# Led_And_Sound.net
KiCad netlist of a schematic drawn in Altium Designer
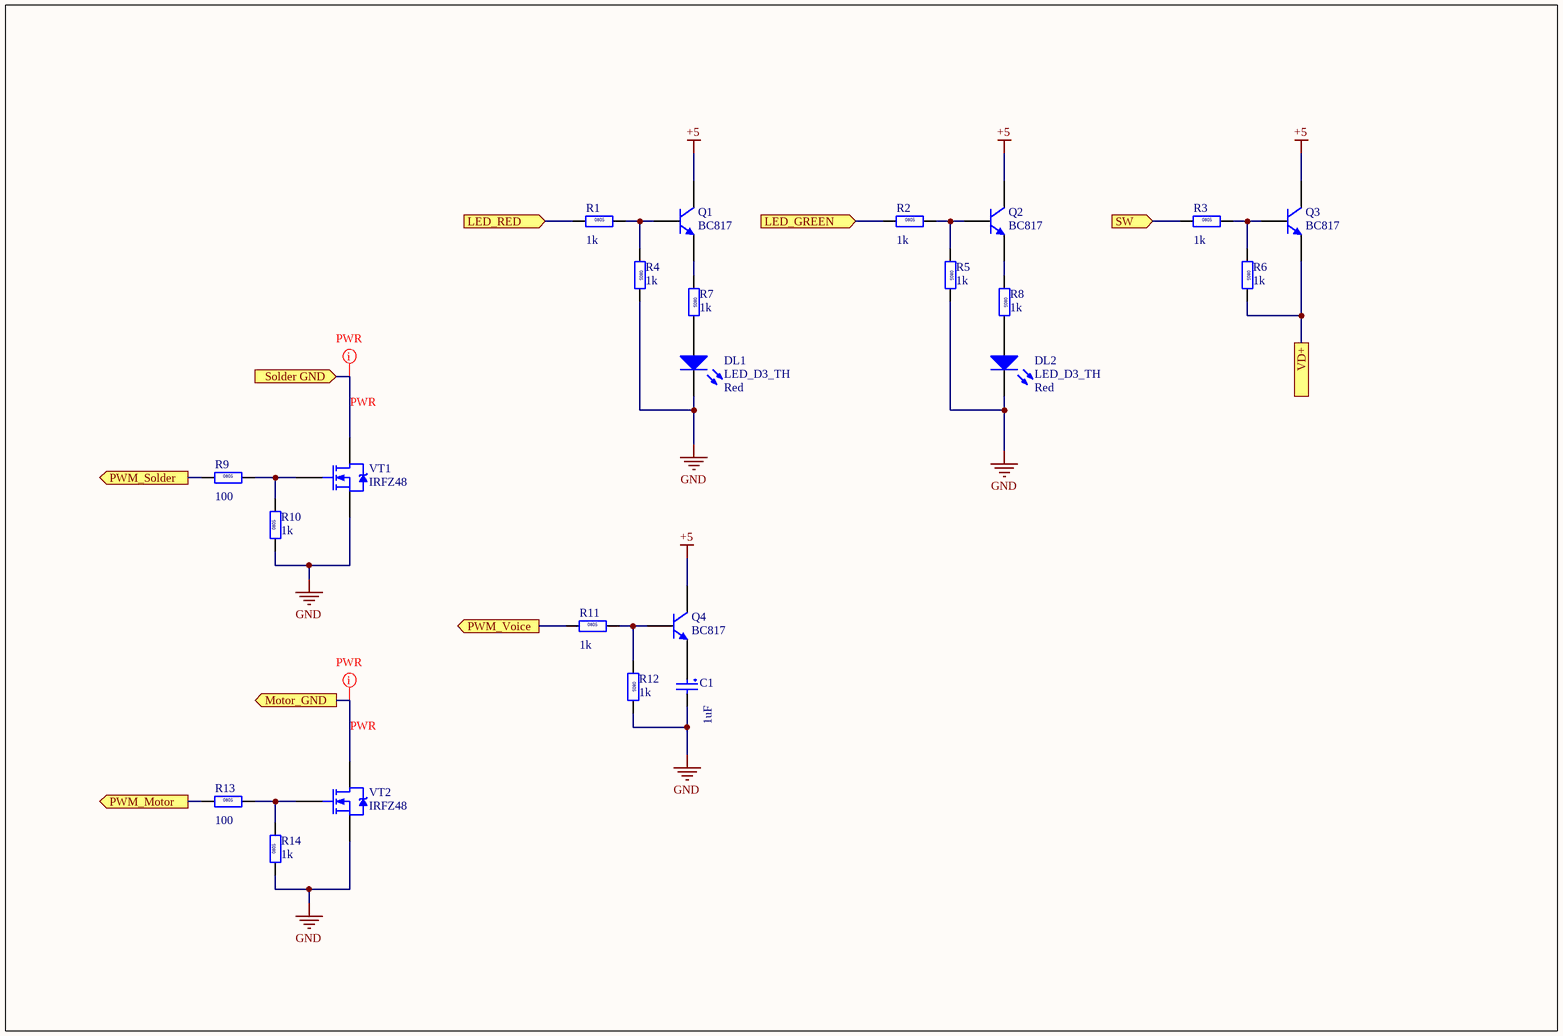
[diagram p0: Led_And_Sound.SchDoc]

(export (version "E")
  (design (tool "Eeschema 10.0.6"))
  (components
    (comp (ref "C1")
      (value "1uF")
      (footprint "ECAP1325")
      (description "Capacitor electrolytic 5 mm pitch, 13*25 body")
      (fields (field (name "Comment") "ECAP-1325"))
      (libsource (lib "Passive") (part "ECAP-1325"))
    )
    (comp (ref "DL1")
      (value "LED_D3_TH")
      (footprint "LED_D3_TH")
      (description "LED Through hole D3mm")
      (fields (field (name "ALTIUM_VALUE") "Red"))
      (libsource (lib "Discrete") (part "LED_D3_TH"))
    )
    (comp (ref "DL2")
      (value "LED_D3_TH")
      (footprint "LED_D3_TH")
      (description "LED Through hole D3mm")
      (fields (field (name "ALTIUM_VALUE") "Red"))
      (libsource (lib "Discrete") (part "LED_D3_TH"))
    )
    (comp (ref "Q1")
      (value "BC817")
      (footprint "SOT23-3M")
      (description "BC817 NPN Transistor")
      (libsource (lib "Discrete") (part "BC817"))
    )
    (comp (ref "Q2")
      (value "BC817")
      (footprint "SOT23-3M")
      (description "BC817 NPN Transistor")
      (libsource (lib "Discrete") (part "BC817"))
    )
    (comp (ref "Q3")
      (value "BC817")
      (footprint "SOT23-3M")
      (description "BC817 NPN Transistor")
      (libsource (lib "Discrete") (part "BC817"))
    )
    (comp (ref "Q4")
      (value "BC817")
      (footprint "SOT23-3M")
      (description "BC817 NPN Transistor")
      (libsource (lib "Discrete") (part "BC817"))
    )
    (comp (ref "R1")
      (value "1k")
      (footprint "RESC2012-0805M")
      (description "Resistor 0805")
      (fields (field (name "Comment") "RESC_0805_R"))
      (libsource (lib "") (part "RESC_0805_R_2"))
    )
    (comp (ref "R2")
      (value "1k")
      (footprint "RESC2012-0805M")
      (description "Resistor 0805")
      (fields (field (name "Comment") "RESC_0805_R"))
      (libsource (lib "") (part "RESC_0805_R_2"))
    )
    (comp (ref "R3")
      (value "1k")
      (footprint "RESC2012-0805M")
      (description "Resistor 0805")
      (fields (field (name "Comment") "RESC_0805_R"))
      (libsource (lib "") (part "RESC_0805_R_2"))
    )
    (comp (ref "R4")
      (value "1k")
      (footprint "RESC2012-0805M")
      (description "Resistor 0805")
      (fields (field (name "Comment") "RESC_0805_R"))
      (libsource (lib "") (part "RESC_0805_R_1"))
    )
    (comp (ref "R5")
      (value "1k")
      (footprint "RESC2012-0805M")
      (description "Resistor 0805")
      (fields (field (name "Comment") "RESC_0805_R"))
      (libsource (lib "") (part "RESC_0805_R_1"))
    )
    (comp (ref "R6")
      (value "1k")
      (footprint "RESC2012-0805M")
      (description "Resistor 0805")
      (fields (field (name "Comment") "RESC_0805_R"))
      (libsource (lib "") (part "RESC_0805_R_1"))
    )
    (comp (ref "R7")
      (value "1k")
      (footprint "RESC2012-0805M")
      (description "Resistor 0805")
      (fields (field (name "Comment") "RESC_0805_R"))
      (libsource (lib "") (part "RESC_0805_R_1"))
    )
    (comp (ref "R8")
      (value "1k")
      (footprint "RESC2012-0805M")
      (description "Resistor 0805")
      (fields (field (name "Comment") "RESC_0805_R"))
      (libsource (lib "") (part "RESC_0805_R_1"))
    )
    (comp (ref "R9")
      (value "100")
      (footprint "RESC2012-0805M")
      (description "Resistor 0805")
      (fields (field (name "Comment") "RESC_0805_R"))
      (libsource (lib "") (part "RESC_0805_R_2"))
    )
    (comp (ref "R10")
      (value "1k")
      (footprint "RESC2012-0805M")
      (description "Resistor 0805")
      (fields (field (name "Comment") "RESC_0805_R"))
      (libsource (lib "Passive") (part "RESC_0805_R"))
    )
    (comp (ref "R11")
      (value "1k")
      (footprint "RESC2012-0805M")
      (description "Resistor 0805")
      (fields (field (name "Comment") "RESC_0805_R"))
      (libsource (lib "") (part "RESC_0805_R_2"))
    )
    (comp (ref "R12")
      (value "1k")
      (footprint "RESC2012-0805M")
      (description "Resistor 0805")
      (fields (field (name "Comment") "RESC_0805_R"))
      (libsource (lib "") (part "RESC_0805_R_1"))
    )
    (comp (ref "R13")
      (value "100")
      (footprint "RESC2012-0805M")
      (description "Resistor 0805")
      (fields (field (name "Comment") "RESC_0805_R"))
      (libsource (lib "") (part "RESC_0805_R_2"))
    )
    (comp (ref "R14")
      (value "1k")
      (footprint "RESC2012-0805M")
      (description "Resistor 0805")
      (fields (field (name "Comment") "RESC_0805_R"))
      (libsource (lib "Passive") (part "RESC_0805_R"))
    )
    (comp (ref "VT1")
      (value "IRFZ48")
      (footprint "TO-220")
      (description "HEXFET N-Channel Power MOSFET")
      (fields (field (name "PUBLISHER") "Altium Limited"))
      (libsource (lib "Discrete") (part "IRFZ48"))
    )
    (comp (ref "VT2")
      (value "IRFZ48")
      (footprint "TO-220")
      (description "HEXFET N-Channel Power MOSFET")
      (fields (field (name "PUBLISHER") "Altium Limited"))
      (libsource (lib "Discrete") (part "IRFZ48"))
    )
  )
  (nets
    (net (code "1") (name "+5") (class "Default")
      (node (ref "Q1") (pin "3") (pinfunction "C_3") (pintype "passive"))
      (node (ref "Q2") (pin "3") (pinfunction "C_3") (pintype "passive"))
      (node (ref "Q3") (pin "3") (pinfunction "C_3") (pintype "passive"))
      (node (ref "Q4") (pin "3") (pinfunction "C_3") (pintype "passive"))
    )
    (net (code "2") (name "/LED_GREEN") (class "Default")
      (node (ref "R2") (pin "1") (pinfunction "1_1") (pintype "passive"))
    )
    (net (code "3") (name "/LED_RED") (class "Default")
      (node (ref "R1") (pin "1") (pinfunction "1_1") (pintype "passive"))
    )
    (net (code "4") (name "/Motor_GND") (class "Default")
      (node (ref "VT2") (pin "2") (pinfunction "D_2") (pintype "passive"))
    )
    (net (code "5") (name "/PWM_Motor") (class "Default")
      (node (ref "R13") (pin "1") (pinfunction "1_1") (pintype "passive"))
    )
    (net (code "6") (name "/PWM_Solder") (class "Default")
      (node (ref "R9") (pin "1") (pinfunction "1_1") (pintype "passive"))
    )
    (net (code "7") (name "/PWM_Voice") (class "Default")
      (node (ref "R11") (pin "1") (pinfunction "1_1") (pintype "passive"))
    )
    (net (code "8") (name "/SW") (class "Default")
      (node (ref "R3") (pin "1") (pinfunction "1_1") (pintype "passive"))
    )
    (net (code "9") (name "/Solder GND") (class "Default")
      (node (ref "VT1") (pin "2") (pinfunction "D_2") (pintype "passive"))
    )
    (net (code "10") (name "/VD+") (class "Default")
      (node (ref "Q3") (pin "2") (pinfunction "E_2") (pintype "passive"))
      (node (ref "R6") (pin "2") (pinfunction "2_2") (pintype "passive"))
    )
    (net (code "11") (name "GND") (class "Default")
      (node (ref "C1") (pin "2") (pinfunction "2_2") (pintype "passive"))
      (node (ref "DL1") (pin "2") (pinfunction "K_2") (pintype "passive"))
      (node (ref "DL2") (pin "2") (pinfunction "K_2") (pintype "passive"))
      (node (ref "R10") (pin "1") (pinfunction "1_1") (pintype "passive"))
      (node (ref "R12") (pin "2") (pinfunction "2_2") (pintype "passive"))
      (node (ref "R14") (pin "1") (pinfunction "1_1") (pintype "passive"))
      (node (ref "R4") (pin "2") (pinfunction "2_2") (pintype "passive"))
      (node (ref "R5") (pin "2") (pinfunction "2_2") (pintype "passive"))
      (node (ref "VT1") (pin "3") (pinfunction "S_3") (pintype "passive"))
      (node (ref "VT2") (pin "3") (pinfunction "S_3") (pintype "passive"))
    )
    (net (code "12") (name "Net-(DL1-A)") (class "Default")
      (node (ref "DL1") (pin "1") (pinfunction "A_1") (pintype "passive"))
      (node (ref "R7") (pin "2") (pinfunction "2_2") (pintype "passive"))
    )
    (net (code "13") (name "Net-(DL2-A)") (class "Default")
      (node (ref "DL2") (pin "1") (pinfunction "A_1") (pintype "passive"))
      (node (ref "R8") (pin "2") (pinfunction "2_2") (pintype "passive"))
    )
    (net (code "14") (name "Net-(Q1-B)") (class "Default")
      (node (ref "Q1") (pin "1") (pinfunction "B_1") (pintype "passive"))
      (node (ref "R1") (pin "2") (pinfunction "2_2") (pintype "passive"))
      (node (ref "R4") (pin "1") (pinfunction "1_1") (pintype "passive"))
    )
    (net (code "15") (name "Net-(Q1-E)") (class "Default")
      (node (ref "Q1") (pin "2") (pinfunction "E_2") (pintype "passive"))
      (node (ref "R7") (pin "1") (pinfunction "1_1") (pintype "passive"))
    )
    (net (code "16") (name "Net-(Q2-B)") (class "Default")
      (node (ref "Q2") (pin "1") (pinfunction "B_1") (pintype "passive"))
      (node (ref "R2") (pin "2") (pinfunction "2_2") (pintype "passive"))
      (node (ref "R5") (pin "1") (pinfunction "1_1") (pintype "passive"))
    )
    (net (code "17") (name "Net-(Q2-E)") (class "Default")
      (node (ref "Q2") (pin "2") (pinfunction "E_2") (pintype "passive"))
      (node (ref "R8") (pin "1") (pinfunction "1_1") (pintype "passive"))
    )
    (net (code "18") (name "Net-(Q3-B)") (class "Default")
      (node (ref "Q3") (pin "1") (pinfunction "B_1") (pintype "passive"))
      (node (ref "R3") (pin "2") (pinfunction "2_2") (pintype "passive"))
      (node (ref "R6") (pin "1") (pinfunction "1_1") (pintype "passive"))
    )
    (net (code "19") (name "Net-(Q4-B)") (class "Default")
      (node (ref "Q4") (pin "1") (pinfunction "B_1") (pintype "passive"))
      (node (ref "R11") (pin "2") (pinfunction "2_2") (pintype "passive"))
      (node (ref "R12") (pin "1") (pinfunction "1_1") (pintype "passive"))
    )
    (net (code "20") (name "Net-(Q4-E)") (class "Default")
      (node (ref "C1") (pin "1") (pinfunction "1_1") (pintype "passive"))
      (node (ref "Q4") (pin "2") (pinfunction "E_2") (pintype "passive"))
    )
    (net (code "21") (name "Net-(VT1-G)") (class "Default")
      (node (ref "R10") (pin "2") (pinfunction "2_2") (pintype "passive"))
      (node (ref "R9") (pin "2") (pinfunction "2_2") (pintype "passive"))
      (node (ref "VT1") (pin "1") (pinfunction "G_1") (pintype "passive"))
    )
    (net (code "22") (name "Net-(VT2-G)") (class "Default")
      (node (ref "R13") (pin "2") (pinfunction "2_2") (pintype "passive"))
      (node (ref "R14") (pin "2") (pinfunction "2_2") (pintype "passive"))
      (node (ref "VT2") (pin "1") (pinfunction "G_1") (pintype "passive"))
    )
  )
)
